# NIBB.net
KiCad netlist of a schematic drawn in EAGLE
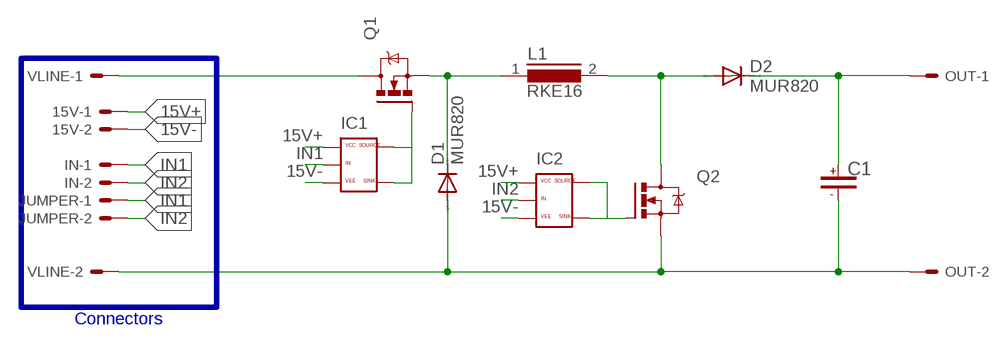
[diagram p0: schematic, sheet 1]

(export (version "E")
  (design (tool "Eeschema 10.0.6"))
  (components
    (comp (ref "15V")
      (value "22-23-2021")
      (footprint "eagle-import:22-23-2021")
      (fields (field (name "MF") "MOLEX"))
      (libsource (lib "eagle-import") (part "22-23-2021"))
    )
    (comp (ref "C1")
      (value "CAPP-UF")
      (footprint "eagle-import:20ROUND40P")
      (libsource (lib "eagle-import") (part "CAPP-UF"))
    )
    (comp (ref "D1")
      (value "MUR820")
      (footprint "eagle-import:C221B1A")
      (libsource (lib "eagle-import") (part "MUR820"))
    )
    (comp (ref "D2")
      (value "MUR820")
      (footprint "eagle-import:C221B1A")
      (libsource (lib "eagle-import") (part "MUR820"))
    )
    (comp (ref "IC1")
      (value "ZXGD3006E6")
      (footprint "eagle-import:SOT23")
      (libsource (lib "eagle-import") (part "ZXGD3006E6"))
    )
    (comp (ref "IC2")
      (value "ZXGD3006E6")
      (footprint "eagle-import:SOT23")
      (libsource (lib "eagle-import") (part "ZXGD3006E6"))
    )
    (comp (ref "IN")
      (value "22-23-2021")
      (footprint "eagle-import:22-23-2021")
      (fields (field (name "MF") "MOLEX"))
      (libsource (lib "eagle-import") (part "22-23-2021"))
    )
    (comp (ref "JUMPER")
      (value "22-23-2021")
      (footprint "eagle-import:22-23-2021")
      (fields (field (name "MF") "MOLEX"))
      (libsource (lib "eagle-import") (part "22-23-2021"))
    )
    (comp (ref "L1")
      (value "RKE16")
      (footprint "eagle-import:RKE16")
      (libsource (lib "eagle-import") (part "RKE16"))
    )
    (comp (ref "OUT")
      (value "22-23-2021")
      (footprint "eagle-import:22-23-2021")
      (fields (field (name "MF") "MOLEX"))
      (libsource (lib "eagle-import") (part "22-23-2021"))
    )
    (comp (ref "Q1")
      (value "IRF640")
      (footprint "eagle-import:TO220BV")
      (libsource (lib "eagle-import") (part "IRF640"))
    )
    (comp (ref "Q2")
      (value "IRF640")
      (footprint "eagle-import:TO220BV")
      (libsource (lib "eagle-import") (part "IRF640"))
    )
    (comp (ref "VLINE")
      (value "22-23-2021")
      (footprint "eagle-import:22-23-2021")
      (fields (field (name "MF") "MOLEX"))
      (libsource (lib "eagle-import") (part "22-23-2021"))
    )
  )
  (nets
    (net (code "1") (name "15V+") (class "Default")
      (node (ref "15V") (pin "1") (pinfunction "S_1") (pintype "passive"))
      (node (ref "IC1") (pin "1") (pinfunction "VCC_1") (pintype "bidirectional"))
      (node (ref "IC2") (pin "1") (pinfunction "VCC_1") (pintype "bidirectional"))
    )
    (net (code "2") (name "15V-") (class "Default")
      (node (ref "15V") (pin "2") (pinfunction "S_2") (pintype "passive"))
      (node (ref "IC1") (pin "3") (pinfunction "VEE_3") (pintype "bidirectional"))
      (node (ref "IC2") (pin "3") (pinfunction "VEE_3") (pintype "bidirectional"))
    )
    (net (code "3") (name "IN1") (class "Default")
      (node (ref "IC1") (pin "2") (pinfunction "IN_2") (pintype "bidirectional"))
      (node (ref "IN") (pin "1") (pinfunction "S_1") (pintype "passive"))
      (node (ref "JUMPER") (pin "1") (pinfunction "S_1") (pintype "passive"))
    )
    (net (code "4") (name "IN2") (class "Default")
      (node (ref "IC2") (pin "2") (pinfunction "IN_2") (pintype "bidirectional"))
      (node (ref "IN") (pin "2") (pinfunction "S_2") (pintype "passive"))
      (node (ref "JUMPER") (pin "2") (pinfunction "S_2") (pintype "passive"))
    )
    (net (code "5") (name "Net-(D1-PadC)") (class "Default")
      (node (ref "D1") (pin "C") (pinfunction "C_C") (pintype "passive"))
      (node (ref "L1") (pin "1") (pinfunction "1_1") (pintype "passive"))
      (node (ref "Q1") (pin "S") (pinfunction "S_S") (pintype "passive"))
    )
    (net (code "6") (name "Net-(D2-PadA)") (class "Default")
      (node (ref "D2") (pin "A") (pinfunction "A_A") (pintype "passive"))
      (node (ref "L1") (pin "2") (pinfunction "2_2") (pintype "passive"))
      (node (ref "Q2") (pin "D") (pinfunction "D_D") (pintype "passive"))
    )
    (net (code "7") (name "Net-(IC1-SINK)") (class "Default")
      (node (ref "IC1") (pin "4") (pinfunction "SINK_4") (pintype "bidirectional"))
      (node (ref "IC1") (pin "6") (pinfunction "SOURCE_6") (pintype "bidirectional"))
      (node (ref "Q1") (pin "G") (pinfunction "G_G") (pintype "passive"))
    )
    (net (code "8") (name "Net-(IC2-SINK)") (class "Default")
      (node (ref "IC2") (pin "4") (pinfunction "SINK_4") (pintype "bidirectional"))
      (node (ref "IC2") (pin "6") (pinfunction "SOURCE_6") (pintype "bidirectional"))
      (node (ref "Q2") (pin "G") (pinfunction "G_G") (pintype "passive"))
    )
    (net (code "9") (name "Net-(OUTA-S)") (class "Default")
      (node (ref "C1") (pin "+") (pinfunction "+_+") (pintype "passive"))
      (node (ref "D2") (pin "C") (pinfunction "C_C") (pintype "passive"))
      (node (ref "OUT") (pin "1") (pinfunction "S_1") (pintype "passive"))
    )
    (net (code "10") (name "Net-(OUTB-S)") (class "Default")
      (node (ref "C1") (pin "-") (pinfunction "-_-") (pintype "passive"))
      (node (ref "D1") (pin "A") (pinfunction "A_A") (pintype "passive"))
      (node (ref "OUT") (pin "2") (pinfunction "S_2") (pintype "passive"))
      (node (ref "Q2") (pin "S") (pinfunction "S_S") (pintype "passive"))
      (node (ref "VLINE") (pin "2") (pinfunction "S_2") (pintype "passive"))
    )
    (net (code "11") (name "Net-(VLINEA-S)") (class "Default")
      (node (ref "Q1") (pin "D") (pinfunction "D_D") (pintype "passive"))
      (node (ref "VLINE") (pin "1") (pinfunction "S_1") (pintype "passive"))
    )
  )
)
